# JTAG_Configuration.net
KiCad netlist of a schematic drawn in Altium Designer
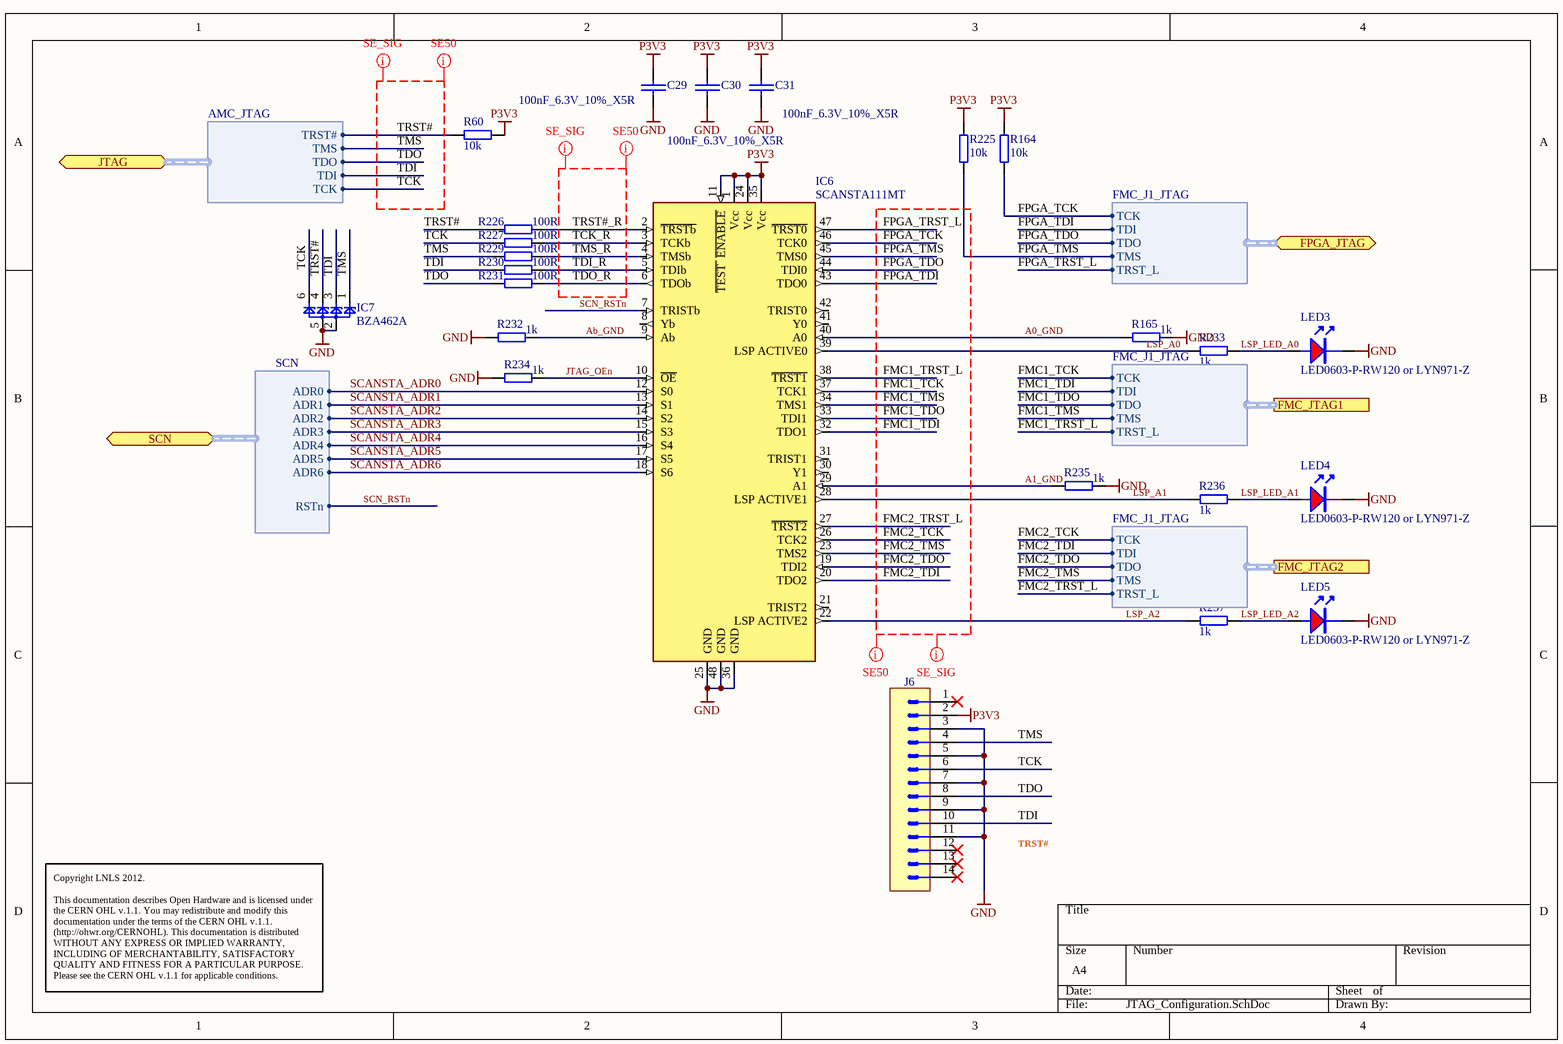
[diagram p0: JTAG_Configuration.SchDoc]

(export (version "E")
  (design (tool "Eeschema 10.0.6"))
  (components
    (comp (ref "C29")
      (value "100nF_6.3V_10%_X5R")
      (footprint "0201C")
      (description "Capacitor SMD")
      (libsource (lib "LIBRARY_SCH") (part "CAP_SMD_0201"))
    )
    (comp (ref "C30")
      (value "100nF_6.3V_10%_X5R")
      (footprint "0201C")
      (description "Capacitor SMD")
      (libsource (lib "LIBRARY_SCH") (part "CAP_SMD_0201"))
    )
    (comp (ref "C31")
      (value "100nF_6.3V_10%_X5R")
      (footprint "0201C")
      (description "Capacitor SMD")
      (libsource (lib "LIBRARY_SCH") (part "CAP_SMD_0201"))
    )
    (comp (ref "IC6")
      (value "SCANSTA111MT")
      (footprint "TSSOP-48")
      (description "Enhanced SCAN Bridge Multidrop Addressable IEEE 1149.1 (JTAG) Port")
      (libsource (lib "LIBRARY_SCH") (part "IFC_SCANSTA111"))
    )
    (comp (ref "IC7")
      (value "BZA462A")
      (footprint "SOT23-6")
      (description "Quadruple 4V ESD transient voltage suppressor")
      (libsource (lib "LIBRARY_SCH") (part "D_TVS_BZA462A"))
    )
    (comp (ref "J6")
      (value "BHMT14S")
      (footprint "BHMT14S")
      (description "Connector 14 Male")
      (fields (field (name "AUTHOR") "CERN DEM JLC"))
      (libsource (lib "Connectors") (part "Connector 14 Male"))
    )
    (comp (ref "LED3")
      (value "LED0603-P-RW120 or LYN971-Z")
      (footprint "led_0603R")
      (description "LED 0603 red")
      (libsource (lib "LIBRARY_SCH") (part "LED_0603R"))
    )
    (comp (ref "LED4")
      (value "LED0603-P-RW120 or LYN971-Z")
      (footprint "led_0603R")
      (description "LED 0603 red")
      (libsource (lib "LIBRARY_SCH") (part "LED_0603R"))
    )
    (comp (ref "LED5")
      (value "LED0603-P-RW120 or LYN971-Z")
      (footprint "led_0603R")
      (description "LED 0603 red")
      (libsource (lib "LIBRARY_SCH") (part "LED_0603R"))
    )
    (comp (ref "R60")
      (value "10k")
      (footprint "0402R")
      (description "SMD Resistor")
      (libsource (lib "LIBRARY_SCH") (part "RES_0402"))
    )
    (comp (ref "R164")
      (value "10k")
      (footprint "0402R")
      (description "SMD Resistor")
      (libsource (lib "LIBRARY_SCH") (part "RES_0402"))
    )
    (comp (ref "R165")
      (value "1k")
      (footprint "0402R")
      (description "SMD Resistor")
      (libsource (lib "LIBRARY_SCH") (part "RES_0402"))
    )
    (comp (ref "R225")
      (value "10k")
      (footprint "0402R")
      (description "SMD Resistor")
      (libsource (lib "LIBRARY_SCH") (part "RES_0402"))
    )
    (comp (ref "R226")
      (value "100R")
      (footprint "0402R")
      (description "SMD Resistor")
      (libsource (lib "LIBRARY_SCH") (part "RES_0402"))
    )
    (comp (ref "R227")
      (value "100R")
      (footprint "0402R")
      (description "SMD Resistor")
      (libsource (lib "LIBRARY_SCH") (part "RES_0402"))
    )
    (comp (ref "R229")
      (value "100R")
      (footprint "0402R")
      (description "SMD Resistor")
      (libsource (lib "LIBRARY_SCH") (part "RES_0402"))
    )
    (comp (ref "R230")
      (value "100R")
      (footprint "0402R")
      (description "SMD Resistor")
      (libsource (lib "LIBRARY_SCH") (part "RES_0402"))
    )
    (comp (ref "R231")
      (value "100R")
      (footprint "0402R")
      (description "SMD Resistor")
      (libsource (lib "LIBRARY_SCH") (part "RES_0402"))
    )
    (comp (ref "R232")
      (value "1k")
      (footprint "0402R")
      (description "SMD Resistor")
      (libsource (lib "LIBRARY_SCH") (part "RES_0402"))
    )
    (comp (ref "R233")
      (value "1k")
      (footprint "0402R")
      (description "SMD Resistor")
      (libsource (lib "LIBRARY_SCH") (part "RES_0402"))
    )
    (comp (ref "R234")
      (value "1k")
      (footprint "0402R")
      (description "SMD Resistor")
      (libsource (lib "LIBRARY_SCH") (part "RES_0402"))
    )
    (comp (ref "R235")
      (value "1k")
      (footprint "0402R")
      (description "SMD Resistor")
      (libsource (lib "LIBRARY_SCH") (part "RES_0402"))
    )
    (comp (ref "R236")
      (value "1k")
      (footprint "0402R")
      (description "SMD Resistor")
      (libsource (lib "LIBRARY_SCH") (part "RES_0402"))
    )
    (comp (ref "R237")
      (value "1k")
      (footprint "0402R")
      (description "SMD Resistor")
      (libsource (lib "LIBRARY_SCH") (part "RES_0402"))
    )
  )
  (nets
    (net (code "4") (name "/A0_GND") (class "Default")
      (node (ref "IC6") (pin "40") (pinfunction "A0_40") (pintype "input"))
      (node (ref "R165") (pin "1") (pinfunction "1_1") (pintype "passive"))
    )
    (net (code "5") (name "/A1_GND") (class "Default")
      (node (ref "IC6") (pin "29") (pinfunction "A1_29") (pintype "input"))
      (node (ref "R235") (pin "1") (pinfunction "1_1") (pintype "passive"))
    )
    (net (code "6") (name "/Ab_GND") (class "Default")
      (node (ref "IC6") (pin "9") (pinfunction "Ab_9") (pintype "input"))
      (node (ref "R232") (pin "2") (pinfunction "2_2") (pintype "passive"))
    )
    (net (code "7") (name "/FMC1_TCK") (class "Default")
      (node (ref "IC6") (pin "37") (pinfunction "TCK1_37") (pintype "output"))
    )
    (net (code "8") (name "/FMC1_TDI") (class "Default")
      (node (ref "IC6") (pin "32") (pinfunction "TDO1_32") (pintype "output"))
    )
    (net (code "9") (name "/FMC1_TDO") (class "Default")
      (node (ref "IC6") (pin "33") (pinfunction "TDI1_33") (pintype "output"))
    )
    (net (code "10") (name "/FMC1_TMS") (class "Default")
      (node (ref "IC6") (pin "34") (pinfunction "TMS1_34") (pintype "output"))
    )
    (net (code "11") (name "/FMC1_TRST_L") (class "Default")
      (node (ref "IC6") (pin "38") (pinfunction "~{TRST1}_38") (pintype "output"))
    )
    (net (code "12") (name "/FMC2_TCK") (class "Default")
      (node (ref "IC6") (pin "26") (pinfunction "TCK2_26") (pintype "output"))
    )
    (net (code "13") (name "/FMC2_TDI") (class "Default")
      (node (ref "IC6") (pin "20") (pinfunction "TDO2_20") (pintype "output"))
    )
    (net (code "14") (name "/FMC2_TDO") (class "Default")
      (node (ref "IC6") (pin "19") (pinfunction "TDI2_19") (pintype "input"))
    )
    (net (code "15") (name "/FMC2_TMS") (class "Default")
      (node (ref "IC6") (pin "23") (pinfunction "TMS2_23") (pintype "output"))
    )
    (net (code "16") (name "/FMC2_TRST_L") (class "Default")
      (node (ref "IC6") (pin "27") (pinfunction "~{TRST2}_27") (pintype "output"))
    )
    (net (code "17") (name "/FPGA_TCK") (class "Default")
      (node (ref "IC6") (pin "46") (pinfunction "TCK0_46") (pintype "output"))
      (node (ref "R164") (pin "1") (pinfunction "1_1") (pintype "passive"))
    )
    (net (code "18") (name "/FPGA_TDI") (class "Default")
      (node (ref "IC6") (pin "43") (pinfunction "TDO0_43") (pintype "output"))
    )
    (net (code "19") (name "/FPGA_TDO") (class "Default")
      (node (ref "IC6") (pin "44") (pinfunction "TDI0_44") (pintype "input"))
    )
    (net (code "20") (name "/FPGA_TMS") (class "Default")
      (node (ref "IC6") (pin "45") (pinfunction "TMS0_45") (pintype "output"))
      (node (ref "R225") (pin "1") (pinfunction "1_1") (pintype "passive"))
    )
    (net (code "21") (name "/FPGA_TRST_L") (class "Default")
      (node (ref "IC6") (pin "47") (pinfunction "~{TRST0}_47") (pintype "output"))
    )
    (net (code "22") (name "/JTAG_OEn") (class "Default")
      (node (ref "IC6") (pin "10") (pinfunction "~{OE}_10") (pintype "input"))
      (node (ref "R234") (pin "2") (pinfunction "2_2") (pintype "passive"))
    )
    (net (code "23") (name "/LSP_A0") (class "Default")
      (node (ref "IC6") (pin "39") (pinfunction "LSP_ACTIVE0_39") (pintype "output"))
      (node (ref "R233") (pin "1") (pinfunction "1_1") (pintype "passive"))
    )
    (net (code "24") (name "/LSP_A1") (class "Default")
      (node (ref "IC6") (pin "28") (pinfunction "LSP_ACTIVE1_28") (pintype "output"))
      (node (ref "R236") (pin "1") (pinfunction "1_1") (pintype "passive"))
    )
    (net (code "25") (name "/LSP_A2") (class "Default")
      (node (ref "IC6") (pin "22") (pinfunction "LSP_ACTIVE2_22") (pintype "output"))
      (node (ref "R237") (pin "1") (pinfunction "1_1") (pintype "passive"))
    )
    (net (code "26") (name "/LSP_LED_A0") (class "Default")
      (node (ref "LED3") (pin "A") (pinfunction "A_A") (pintype "passive"))
      (node (ref "R233") (pin "2") (pinfunction "2_2") (pintype "passive"))
    )
    (net (code "27") (name "/LSP_LED_A1") (class "Default")
      (node (ref "LED4") (pin "A") (pinfunction "A_A") (pintype "passive"))
      (node (ref "R236") (pin "2") (pinfunction "2_2") (pintype "passive"))
    )
    (net (code "28") (name "/LSP_LED_A2") (class "Default")
      (node (ref "LED5") (pin "A") (pinfunction "A_A") (pintype "passive"))
      (node (ref "R237") (pin "2") (pinfunction "2_2") (pintype "passive"))
    )
    (net (code "29") (name "/SCANSTA_ADR0") (class "Default")
      (node (ref "IC6") (pin "12") (pinfunction "S0_12") (pintype "input"))
    )
    (net (code "30") (name "/SCANSTA_ADR1") (class "Default")
      (node (ref "IC6") (pin "13") (pinfunction "S1_13") (pintype "input"))
    )
    (net (code "31") (name "/SCANSTA_ADR2") (class "Default")
      (node (ref "IC6") (pin "14") (pinfunction "S2_14") (pintype "input"))
    )
    (net (code "32") (name "/SCANSTA_ADR3") (class "Default")
      (node (ref "IC6") (pin "15") (pinfunction "S3_15") (pintype "input"))
    )
    (net (code "33") (name "/SCANSTA_ADR4") (class "Default")
      (node (ref "IC6") (pin "16") (pinfunction "S4_16") (pintype "input"))
    )
    (net (code "34") (name "/SCANSTA_ADR5") (class "Default")
      (node (ref "IC6") (pin "17") (pinfunction "S5_17") (pintype "input"))
    )
    (net (code "35") (name "/SCANSTA_ADR6") (class "Default")
      (node (ref "IC6") (pin "18") (pinfunction "S6_18") (pintype "input"))
    )
    (net (code "36") (name "/SCN_RSTn") (class "Default")
      (node (ref "IC6") (pin "7") (pinfunction "TRISTb_7") (pintype "input"))
    )
    (net (code "37") (name "/TCK") (class "Default")
      (node (ref "IC7") (pin "6") (pinfunction "6_6") (pintype "passive"))
      (node (ref "J6") (pin "6") (pinfunction "6_6") (pintype "passive"))
      (node (ref "R227") (pin "1") (pinfunction "1_1") (pintype "passive"))
    )
    (net (code "38") (name "/TCK_R") (class "Default")
      (node (ref "IC6") (pin "3") (pinfunction "TCKb_3") (pintype "input"))
      (node (ref "R227") (pin "2") (pinfunction "2_2") (pintype "passive"))
    )
    (net (code "39") (name "/TDI") (class "Default")
      (node (ref "IC7") (pin "3") (pinfunction "3_3") (pintype "passive"))
      (node (ref "J6") (pin "10") (pinfunction "10_10") (pintype "passive"))
      (node (ref "R230") (pin "1") (pinfunction "1_1") (pintype "passive"))
    )
    (net (code "40") (name "/TDI_R") (class "Default")
      (node (ref "IC6") (pin "5") (pinfunction "TDIb_5") (pintype "input"))
      (node (ref "R230") (pin "2") (pinfunction "2_2") (pintype "passive"))
    )
    (net (code "41") (name "/TDO") (class "Default")
      (node (ref "J6") (pin "8") (pinfunction "8_8") (pintype "passive"))
      (node (ref "R231") (pin "1") (pinfunction "1_1") (pintype "passive"))
    )
    (net (code "42") (name "/TDO_R") (class "Default")
      (node (ref "IC6") (pin "6") (pinfunction "TDOb_6") (pintype "output"))
      (node (ref "R231") (pin "2") (pinfunction "2_2") (pintype "passive"))
    )
    (net (code "43") (name "/TMS") (class "Default")
      (node (ref "IC7") (pin "1") (pinfunction "1_1") (pintype "passive"))
      (node (ref "J6") (pin "4") (pinfunction "4_4") (pintype "passive"))
      (node (ref "R229") (pin "1") (pinfunction "1_1") (pintype "passive"))
    )
    (net (code "44") (name "/TMS_R") (class "Default")
      (node (ref "IC6") (pin "4") (pinfunction "TMSb_4") (pintype "input"))
      (node (ref "R229") (pin "2") (pinfunction "2_2") (pintype "passive"))
    )
    (net (code "45") (name "/TRST#") (class "Default")
      (node (ref "IC7") (pin "4") (pinfunction "4_4") (pintype "passive"))
      (node (ref "R226") (pin "1") (pinfunction "1_1") (pintype "passive"))
      (node (ref "R60") (pin "2") (pinfunction "2_2") (pintype "passive"))
    )
    (net (code "46") (name "/TRST#_R") (class "Default")
      (node (ref "IC6") (pin "2") (pinfunction "~{TRSTb}_2") (pintype "input"))
      (node (ref "R226") (pin "2") (pinfunction "2_2") (pintype "passive"))
    )
    (net (code "50") (name "GND") (class "Default")
      (node (ref "C29") (pin "2") (pinfunction "2_2") (pintype "passive"))
      (node (ref "C30") (pin "2") (pinfunction "2_2") (pintype "passive"))
      (node (ref "C31") (pin "2") (pinfunction "2_2") (pintype "passive"))
      (node (ref "IC6") (pin "25") (pinfunction "GND_25") (pintype "power_in"))
      (node (ref "IC6") (pin "36") (pinfunction "GND_36") (pintype "power_in"))
      (node (ref "IC6") (pin "48") (pinfunction "GND_48") (pintype "power_in"))
      (node (ref "IC7") (pin "2") (pinfunction "2_2") (pintype "passive"))
      (node (ref "IC7") (pin "5") (pinfunction "5_5") (pintype "passive"))
      (node (ref "J6") (pin "11") (pinfunction "11_11") (pintype "passive"))
      (node (ref "J6") (pin "3") (pinfunction "3_3") (pintype "passive"))
      (node (ref "J6") (pin "5") (pinfunction "5_5") (pintype "passive"))
      (node (ref "J6") (pin "7") (pinfunction "7_7") (pintype "passive"))
      (node (ref "J6") (pin "9") (pinfunction "9_9") (pintype "passive"))
      (node (ref "LED3") (pin "K") (pinfunction "K_K") (pintype "passive"))
      (node (ref "LED4") (pin "K") (pinfunction "K_K") (pintype "passive"))
      (node (ref "LED5") (pin "K") (pinfunction "K_K") (pintype "passive"))
      (node (ref "R165") (pin "2") (pinfunction "2_2") (pintype "passive"))
      (node (ref "R232") (pin "1") (pinfunction "1_1") (pintype "passive"))
      (node (ref "R234") (pin "1") (pinfunction "1_1") (pintype "passive"))
      (node (ref "R235") (pin "2") (pinfunction "2_2") (pintype "passive"))
    )
    (net (code "51") (name "P3V3") (class "Default")
      (node (ref "C29") (pin "1") (pinfunction "1_1") (pintype "passive"))
      (node (ref "C30") (pin "1") (pinfunction "1_1") (pintype "passive"))
      (node (ref "C31") (pin "1") (pinfunction "1_1") (pintype "passive"))
      (node (ref "IC6") (pin "1") (pinfunction "Vcc_1") (pintype "power_in"))
      (node (ref "IC6") (pin "11") (pinfunction "~{TEST_}_~{ENABLE}_11") (pintype "input"))
      (node (ref "IC6") (pin "24") (pinfunction "Vcc_24") (pintype "power_in"))
      (node (ref "IC6") (pin "35") (pinfunction "Vcc_35") (pintype "power_in"))
      (node (ref "J6") (pin "2") (pinfunction "2_2") (pintype "passive"))
      (node (ref "R164") (pin "2") (pinfunction "2_2") (pintype "passive"))
      (node (ref "R225") (pin "2") (pinfunction "2_2") (pintype "passive"))
      (node (ref "R60") (pin "1") (pinfunction "1_1") (pintype "passive"))
    )
    (net (code "52") (name "unconnected-(IC6-TRIST0-Pad42)") (class "Default")
      (node (ref "IC6") (pin "42") (pinfunction "TRIST0_42") (pintype "output"))
    )
    (net (code "53") (name "unconnected-(IC6-TRIST1-Pad31)") (class "Default")
      (node (ref "IC6") (pin "31") (pinfunction "TRIST1_31") (pintype "output"))
    )
    (net (code "54") (name "unconnected-(IC6-TRIST2-Pad21)") (class "Default")
      (node (ref "IC6") (pin "21") (pinfunction "TRIST2_21") (pintype "output"))
    )
    (net (code "55") (name "unconnected-(IC6-Y0-Pad41)") (class "Default")
      (node (ref "IC6") (pin "41") (pinfunction "Y0_41") (pintype "output"))
    )
    (net (code "56") (name "unconnected-(IC6-Y1-Pad30)") (class "Default")
      (node (ref "IC6") (pin "30") (pinfunction "Y1_30") (pintype "output"))
    )
    (net (code "57") (name "unconnected-(IC6-Yb-Pad8)") (class "Default")
      (node (ref "IC6") (pin "8") (pinfunction "Yb_8") (pintype "output"))
    )
    (net (code "58") (name "unconnected-(J6-Pad1)") (class "Default")
      (node (ref "J6") (pin "1") (pinfunction "1_1") (pintype "passive+no_connect"))
    )
    (net (code "59") (name "unconnected-(J6-Pad12)") (class "Default")
      (node (ref "J6") (pin "12") (pinfunction "12_12") (pintype "passive+no_connect"))
    )
    (net (code "60") (name "unconnected-(J6-Pad13)") (class "Default")
      (node (ref "J6") (pin "13") (pinfunction "13_13") (pintype "passive+no_connect"))
    )
    (net (code "61") (name "unconnected-(J6-Pad14)") (class "Default")
      (node (ref "J6") (pin "14") (pinfunction "14_14") (pintype "passive+no_connect"))
    )
  )
)
